# Control.net
KiCad netlist of a schematic drawn in Altium Designer
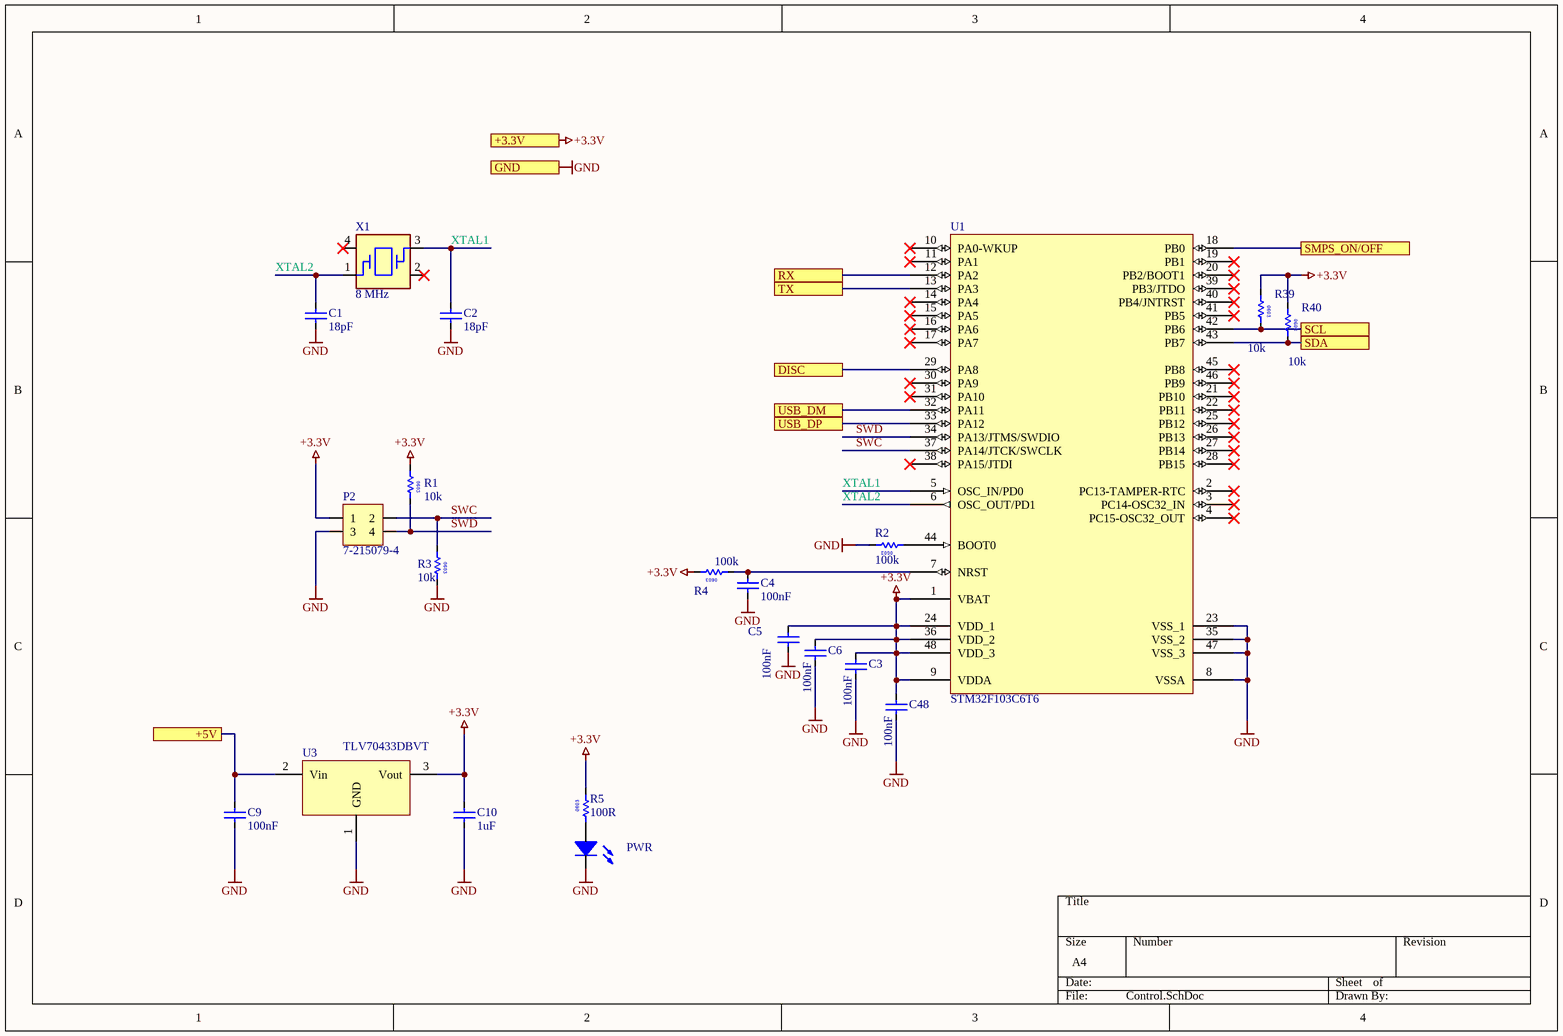
[diagram p0: Control.SchDoc]

(export (version "E")
  (design (tool "Eeschema 10.0.6"))
  (components
    (comp (ref "C1")
      (value "18pF")
      (footprint "CAPC1608N")
      (description "MLCC, 18 pF, ± 5%, C0G / NP0, 50 V, 0603")
      (fields (field (name "PART NUMBER") "C0000124") (field (name "VOLTAGE") "50"))
      (libsource (lib "KTU_DB") (part "C_SM"))
    )
    (comp (ref "C2")
      (value "18pF")
      (footprint "CAPC1608N")
      (description "MLCC, 18 pF, ± 5%, C0G / NP0, 50 V, 0603")
      (fields (field (name "PART NUMBER") "C0000124") (field (name "VOLTAGE") "50"))
      (libsource (lib "KTU_DB") (part "C_SM"))
    )
    (comp (ref "C3")
      (value "100nF")
      (footprint "C0603V")
      (description "MLCC, 0.1uF 16V 10% X7R 0603")
      (fields (field (name "PART NUMBER") "C0000005") (field (name "VOLTAGE") "16"))
      (libsource (lib "KTU_DB") (part "C_SM"))
    )
    (comp (ref "C4")
      (value "100nF")
      (footprint "C0603V")
      (description "MLCC, 0.1uF 16V 10% X7R 0603")
      (fields (field (name "PART NUMBER") "C0000005") (field (name "VOLTAGE") "16"))
      (libsource (lib "KTU_DB") (part "C_SM"))
    )
    (comp (ref "C5")
      (value "100nF")
      (footprint "C0603V")
      (description "MLCC, 0.1uF 16V 10% X7R 0603")
      (fields (field (name "PART NUMBER") "C0000005") (field (name "VOLTAGE") "16"))
      (libsource (lib "KTU_DB") (part "C_SM"))
    )
    (comp (ref "C6")
      (value "100nF")
      (footprint "C0603V")
      (description "MLCC, 0.1uF 16V 10% X7R 0603")
      (fields (field (name "PART NUMBER") "C0000005") (field (name "VOLTAGE") "16"))
      (libsource (lib "KTU_DB") (part "C_SM"))
    )
    (comp (ref "C9")
      (value "100nF")
      (footprint "C0603V")
      (description "MLCC, 0.1uF 16V 10% X7R 0603")
      (fields (field (name "PART NUMBER") "C0000005") (field (name "VOLTAGE") "16"))
      (libsource (lib "KTU_DB") (part "C_SM"))
    )
    (comp (ref "C10")
      (value "1uF")
      (footprint "CAPC2012N")
      (description "MLCC, 0805, X5R, 16V, 1UF")
      (fields (field (name "PART NUMBER") "C0000037") (field (name "VOLTAGE") "16"))
      (libsource (lib "KTU_DB") (part "C_SM"))
    )
    (comp (ref "C48")
      (value "100nF")
      (footprint "C0603V")
      (description "MLCC, 0.1uF 16V 10% X7R 0603")
      (fields (field (name "PART NUMBER") "C0000005") (field (name "VOLTAGE") "16"))
      (libsource (lib "KTU_DB") (part "C_SM"))
    )
    (comp (ref "P2")
      (value "7-215079-4")
      (footprint "ZIP-T4")
      (description "Micro-match SOCKET, TOP ENTRY, 4WAY PTH, 1.27mm")
      (fields (field (name "MANUFACTURER") "TE Connectivity") (field (name "PART NUMBER") "J0000107"))
      (libsource (lib "KTU_DB") (part "HDR2X2"))
    )
    (comp (ref "PWR")
      (value "KPHCM-2012SGC-T")
      (footprint "D0805")
      (description "LED, SMD, 0805, GREEN, 25mcd")
      (fields (field (name "PART NUMBER") "D0000030") (field (name "MANUFACTURER") "KINGBRIGHT"))
      (libsource (lib "KTU_DB") (part "LED"))
    )
    (comp (ref "R1")
      (value "10k")
      (footprint "RESC1608N")
      (description "Res, 10K 0.063W 75V 1%  0603")
      (fields (field (name "TOLERANCE") "±1%") (field (name "POWER") "0.063W"))
      (libsource (lib "KTU_DB") (part "R0603"))
    )
    (comp (ref "R2")
      (value "100k")
      (footprint "RESC1608N")
      (description "Res, 100K 5% 0603 1/10W")
      (fields (field (name "TOLERANCE") "±1%") (field (name "POWER") "1/10W"))
      (libsource (lib "KTU_DB") (part "R0603"))
    )
    (comp (ref "R3")
      (value "10k")
      (footprint "RESC1608N")
      (description "Res, 10K 0.063W 75V 1%  0603")
      (fields (field (name "TOLERANCE") "±1%") (field (name "POWER") "0.063W"))
      (libsource (lib "KTU_DB") (part "R0603"))
    )
    (comp (ref "R4")
      (value "100k")
      (footprint "RESC1608N")
      (description "Res, 100K 5% 0603 1/10W")
      (fields (field (name "TOLERANCE") "±1%") (field (name "POWER") "1/10W"))
      (libsource (lib "KTU_DB") (part "R0603"))
    )
    (comp (ref "R5")
      (value "100R")
      (footprint "RESC1608N")
      (description "Res, 100R 5% 0603 1/10W")
      (fields (field (name "TOLERANCE") "±5%") (field (name "POWER") "1/10W"))
      (libsource (lib "KTU_DB") (part "R0603"))
    )
    (comp (ref "R39")
      (value "10k")
      (footprint "RESC1608N")
      (description "Res, 10K 0.063W 75V 1%  0603")
      (fields (field (name "TOLERANCE") "±1%") (field (name "POWER") "0.063W"))
      (libsource (lib "KTU_DB") (part "R0603"))
    )
    (comp (ref "R40")
      (value "10k")
      (footprint "RESC1608N")
      (description "Res, 10K 0.063W 75V 1%  0603")
      (fields (field (name "TOLERANCE") "±1%") (field (name "POWER") "0.063W"))
      (libsource (lib "KTU_DB") (part "R0603"))
    )
    (comp (ref "U1")
      (value "STM32F103C6T6")
      (footprint "LQFP48_N")
      (description "STM32 ARM-based 32-bit MCU with 32 Kbytes Flash, 48-pin LQFP, Industrial Temperature")
      (fields (field (name "PUBLISHER") "Altium Limited"))
      (libsource (lib "ST Microcontroller 32-Bit STM32") (part "STM32F103C6T6"))
    )
    (comp (ref "U3")
      (value "TLV70433DBVT")
      (footprint "SO-G5/P.95")
      (description "LDO, 3.3V, 150MA, SOT23-5 Vin - 24V")
      (fields (field (name "MANUFACTURER") "Texas Instruments"))
      (libsource (lib "KTU_DB") (part "VOLTREG2"))
    )
    (comp (ref "X1")
      (value "8 MHz")
      (footprint "2SMX-3SMXB")
      (description "CRYSTAL, 8M, 18PF CL, 6X3.6MM SMT")
      (fields (field (name "PART NUMBER") "M0000014") (field (name "TOLERANCE") "± 20ppm"))
      (libsource (lib "KTU_DB") (part "XTAL2"))
    )
  )
  (nets
    (net (code "1") (name "+3.3V") (class "Default")
      (node (ref "C10") (pin "2") (pinfunction "2_2") (pintype "passive"))
      (node (ref "C3") (pin "2") (pinfunction "2_2") (pintype "passive"))
      (node (ref "C48") (pin "2") (pinfunction "2_2") (pintype "passive"))
      (node (ref "C5") (pin "2") (pinfunction "2_2") (pintype "passive"))
      (node (ref "C6") (pin "2") (pinfunction "2_2") (pintype "passive"))
      (node (ref "P2") (pin "1") (pinfunction "1_1") (pintype "passive"))
      (node (ref "R1") (pin "1") (pinfunction "1_1") (pintype "passive"))
      (node (ref "R39") (pin "1") (pinfunction "1_1") (pintype "passive"))
      (node (ref "R4") (pin "2") (pinfunction "2_2") (pintype "passive"))
      (node (ref "R40") (pin "1") (pinfunction "1_1") (pintype "passive"))
      (node (ref "R5") (pin "2") (pinfunction "2_2") (pintype "passive"))
      (node (ref "U1") (pin "1") (pinfunction "VBAT_1") (pintype "power_in"))
      (node (ref "U1") (pin "24") (pinfunction "VDD_1_24") (pintype "power_in"))
      (node (ref "U1") (pin "36") (pinfunction "VDD_2_36") (pintype "power_in"))
      (node (ref "U1") (pin "48") (pinfunction "VDD_3_48") (pintype "power_in"))
      (node (ref "U1") (pin "9") (pinfunction "VDDA_9") (pintype "power_in"))
      (node (ref "U3") (pin "3") (pinfunction "Vout_3") (pintype "passive"))
    )
    (net (code "2") (name "/+5V") (class "Default")
      (node (ref "C9") (pin "2") (pinfunction "2_2") (pintype "passive"))
      (node (ref "U3") (pin "2") (pinfunction "Vin_2") (pintype "passive"))
    )
    (net (code "3") (name "/DISC") (class "Default")
      (node (ref "U1") (pin "29") (pinfunction "PA8_29") (pintype "bidirectional"))
    )
    (net (code "4") (name "/RX") (class "Default")
      (node (ref "U1") (pin "12") (pinfunction "PA2_12") (pintype "bidirectional"))
    )
    (net (code "5") (name "/SCL") (class "Default")
      (node (ref "R39") (pin "2") (pinfunction "2_2") (pintype "passive"))
      (node (ref "U1") (pin "42") (pinfunction "PB6_42") (pintype "bidirectional"))
    )
    (net (code "6") (name "/SDA") (class "Default")
      (node (ref "R40") (pin "2") (pinfunction "2_2") (pintype "passive"))
      (node (ref "U1") (pin "43") (pinfunction "PB7_43") (pintype "bidirectional"))
    )
    (net (code "7") (name "/SMPS_ON{slash}OFF") (class "Default")
      (node (ref "U1") (pin "18") (pinfunction "PB0_18") (pintype "bidirectional"))
    )
    (net (code "8") (name "/SWC") (class "Default")
      (node (ref "P2") (pin "2") (pinfunction "2_2") (pintype "passive"))
      (node (ref "R3") (pin "1") (pinfunction "1_1") (pintype "passive"))
      (node (ref "U1") (pin "37") (pinfunction "PA14/JTCK/SWCLK_37") (pintype "bidirectional"))
    )
    (net (code "9") (name "/SWD") (class "Default")
      (node (ref "P2") (pin "4") (pinfunction "4_4") (pintype "passive"))
      (node (ref "R1") (pin "2") (pinfunction "2_2") (pintype "passive"))
      (node (ref "U1") (pin "34") (pinfunction "PA13/JTMS/SWDIO_34") (pintype "bidirectional"))
    )
    (net (code "10") (name "/TX") (class "Default")
      (node (ref "U1") (pin "13") (pinfunction "PA3_13") (pintype "bidirectional"))
    )
    (net (code "11") (name "/USB_DM") (class "Default")
      (node (ref "U1") (pin "32") (pinfunction "PA11_32") (pintype "bidirectional"))
    )
    (net (code "12") (name "/USB_DP") (class "Default")
      (node (ref "U1") (pin "33") (pinfunction "PA12_33") (pintype "bidirectional"))
    )
    (net (code "13") (name "/XTAL1") (class "Default")
      (node (ref "C2") (pin "2") (pinfunction "2_2") (pintype "passive"))
      (node (ref "U1") (pin "5") (pinfunction "OSC_IN/PD0_5") (pintype "input"))
      (node (ref "X1") (pin "3") (pinfunction "3_3") (pintype "passive"))
    )
    (net (code "14") (name "/XTAL2") (class "Default")
      (node (ref "C1") (pin "2") (pinfunction "2_2") (pintype "passive"))
      (node (ref "U1") (pin "6") (pinfunction "OSC_OUT/PD1_6") (pintype "output"))
      (node (ref "X1") (pin "1") (pinfunction "1_1") (pintype "passive"))
    )
    (net (code "15") (name "GND") (class "Default")
      (node (ref "C1") (pin "1") (pinfunction "1_1") (pintype "passive"))
      (node (ref "C10") (pin "1") (pinfunction "1_1") (pintype "passive"))
      (node (ref "C2") (pin "1") (pinfunction "1_1") (pintype "passive"))
      (node (ref "C3") (pin "1") (pinfunction "1_1") (pintype "passive"))
      (node (ref "C4") (pin "1") (pinfunction "1_1") (pintype "passive"))
      (node (ref "C48") (pin "1") (pinfunction "1_1") (pintype "passive"))
      (node (ref "C5") (pin "1") (pinfunction "1_1") (pintype "passive"))
      (node (ref "C6") (pin "1") (pinfunction "1_1") (pintype "passive"))
      (node (ref "C9") (pin "1") (pinfunction "1_1") (pintype "passive"))
      (node (ref "P2") (pin "3") (pinfunction "3_3") (pintype "passive"))
      (node (ref "PWR") (pin "2") (pinfunction "2_2") (pintype "passive"))
      (node (ref "R2") (pin "2") (pinfunction "2_2") (pintype "passive"))
      (node (ref "R3") (pin "2") (pinfunction "2_2") (pintype "passive"))
      (node (ref "U1") (pin "23") (pinfunction "VSS_1_23") (pintype "power_in"))
      (node (ref "U1") (pin "35") (pinfunction "VSS_2_35") (pintype "power_in"))
      (node (ref "U1") (pin "47") (pinfunction "VSS_3_47") (pintype "power_in"))
      (node (ref "U1") (pin "8") (pinfunction "VSSA_8") (pintype "power_in"))
      (node (ref "U3") (pin "1") (pinfunction "GND_1") (pintype "passive"))
    )
    (net (code "16") (name "Net-(PWR-Pad1)") (class "Default")
      (node (ref "PWR") (pin "1") (pinfunction "1_1") (pintype "passive"))
      (node (ref "R5") (pin "1") (pinfunction "1_1") (pintype "passive"))
    )
    (net (code "17") (name "Net-(U1-BOOT0)") (class "Default")
      (node (ref "R2") (pin "1") (pinfunction "1_1") (pintype "passive"))
      (node (ref "U1") (pin "44") (pinfunction "BOOT0_44") (pintype "input"))
    )
    (net (code "18") (name "Net-(U1-NRST)") (class "Default")
      (node (ref "C4") (pin "2") (pinfunction "2_2") (pintype "passive"))
      (node (ref "R4") (pin "1") (pinfunction "1_1") (pintype "passive"))
      (node (ref "U1") (pin "7") (pinfunction "NRST_7") (pintype "bidirectional"))
    )
    (net (code "19") (name "unconnected-(U1-PA0-WKUP-Pad10)") (class "Default")
      (node (ref "U1") (pin "10") (pinfunction "PA0-WKUP_10") (pintype "bidirectional+no_connect"))
    )
    (net (code "20") (name "unconnected-(U1-PA1-Pad11)") (class "Default")
      (node (ref "U1") (pin "11") (pinfunction "PA1_11") (pintype "bidirectional+no_connect"))
    )
    (net (code "21") (name "unconnected-(U1-PA4-Pad14)") (class "Default")
      (node (ref "U1") (pin "14") (pinfunction "PA4_14") (pintype "bidirectional+no_connect"))
    )
    (net (code "22") (name "unconnected-(U1-PA5-Pad15)") (class "Default")
      (node (ref "U1") (pin "15") (pinfunction "PA5_15") (pintype "bidirectional+no_connect"))
    )
    (net (code "23") (name "unconnected-(U1-PA6-Pad16)") (class "Default")
      (node (ref "U1") (pin "16") (pinfunction "PA6_16") (pintype "bidirectional+no_connect"))
    )
    (net (code "24") (name "unconnected-(U1-PA7-Pad17)") (class "Default")
      (node (ref "U1") (pin "17") (pinfunction "PA7_17") (pintype "bidirectional+no_connect"))
    )
    (net (code "25") (name "unconnected-(U1-PA9-Pad30)") (class "Default")
      (node (ref "U1") (pin "30") (pinfunction "PA9_30") (pintype "bidirectional+no_connect"))
    )
    (net (code "26") (name "unconnected-(U1-PA10-Pad31)") (class "Default")
      (node (ref "U1") (pin "31") (pinfunction "PA10_31") (pintype "bidirectional+no_connect"))
    )
    (net (code "27") (name "unconnected-(U1-PA15{slash}JTDI-Pad38)") (class "Default")
      (node (ref "U1") (pin "38") (pinfunction "PA15/JTDI_38") (pintype "bidirectional+no_connect"))
    )
    (net (code "28") (name "unconnected-(U1-PB1-Pad19)") (class "Default")
      (node (ref "U1") (pin "19") (pinfunction "PB1_19") (pintype "bidirectional+no_connect"))
    )
    (net (code "29") (name "unconnected-(U1-PB2{slash}BOOT1-Pad20)") (class "Default")
      (node (ref "U1") (pin "20") (pinfunction "PB2/BOOT1_20") (pintype "bidirectional+no_connect"))
    )
    (net (code "30") (name "unconnected-(U1-PB3{slash}JTDO-Pad39)") (class "Default")
      (node (ref "U1") (pin "39") (pinfunction "PB3/JTDO_39") (pintype "bidirectional+no_connect"))
    )
    (net (code "31") (name "unconnected-(U1-PB4{slash}JNTRST-Pad40)") (class "Default")
      (node (ref "U1") (pin "40") (pinfunction "PB4/JNTRST_40") (pintype "bidirectional+no_connect"))
    )
    (net (code "32") (name "unconnected-(U1-PB5-Pad41)") (class "Default")
      (node (ref "U1") (pin "41") (pinfunction "PB5_41") (pintype "bidirectional+no_connect"))
    )
    (net (code "33") (name "unconnected-(U1-PB8-Pad45)") (class "Default")
      (node (ref "U1") (pin "45") (pinfunction "PB8_45") (pintype "bidirectional+no_connect"))
    )
    (net (code "34") (name "unconnected-(U1-PB9-Pad46)") (class "Default")
      (node (ref "U1") (pin "46") (pinfunction "PB9_46") (pintype "bidirectional+no_connect"))
    )
    (net (code "35") (name "unconnected-(U1-PB10-Pad21)") (class "Default")
      (node (ref "U1") (pin "21") (pinfunction "PB10_21") (pintype "bidirectional+no_connect"))
    )
    (net (code "36") (name "unconnected-(U1-PB11-Pad22)") (class "Default")
      (node (ref "U1") (pin "22") (pinfunction "PB11_22") (pintype "bidirectional+no_connect"))
    )
    (net (code "37") (name "unconnected-(U1-PB12-Pad25)") (class "Default")
      (node (ref "U1") (pin "25") (pinfunction "PB12_25") (pintype "bidirectional+no_connect"))
    )
    (net (code "38") (name "unconnected-(U1-PB13-Pad26)") (class "Default")
      (node (ref "U1") (pin "26") (pinfunction "PB13_26") (pintype "bidirectional+no_connect"))
    )
    (net (code "39") (name "unconnected-(U1-PB14-Pad27)") (class "Default")
      (node (ref "U1") (pin "27") (pinfunction "PB14_27") (pintype "bidirectional+no_connect"))
    )
    (net (code "40") (name "unconnected-(U1-PB15-Pad28)") (class "Default")
      (node (ref "U1") (pin "28") (pinfunction "PB15_28") (pintype "bidirectional+no_connect"))
    )
    (net (code "41") (name "unconnected-(U1-PC13-TAMPER-RTC-Pad2)") (class "Default")
      (node (ref "U1") (pin "2") (pinfunction "PC13-TAMPER-RTC_2") (pintype "bidirectional+no_connect"))
    )
    (net (code "42") (name "unconnected-(U1-PC14-OSC32_IN-Pad3)") (class "Default")
      (node (ref "U1") (pin "3") (pinfunction "PC14-OSC32_IN_3") (pintype "bidirectional+no_connect"))
    )
    (net (code "43") (name "unconnected-(U1-PC15-OSC32_OUT-Pad4)") (class "Default")
      (node (ref "U1") (pin "4") (pinfunction "PC15-OSC32_OUT_4") (pintype "bidirectional+no_connect"))
    )
    (net (code "44") (name "unconnected-(X1-Pad2)") (class "Default")
      (node (ref "X1") (pin "2") (pinfunction "2_2") (pintype "passive+no_connect"))
    )
    (net (code "45") (name "unconnected-(X1-Pad4)") (class "Default")
      (node (ref "X1") (pin "4") (pinfunction "4_4") (pintype "passive+no_connect"))
    )
  )
)
